# ignition2.net
KiCad netlist of a schematic drawn in EAGLE
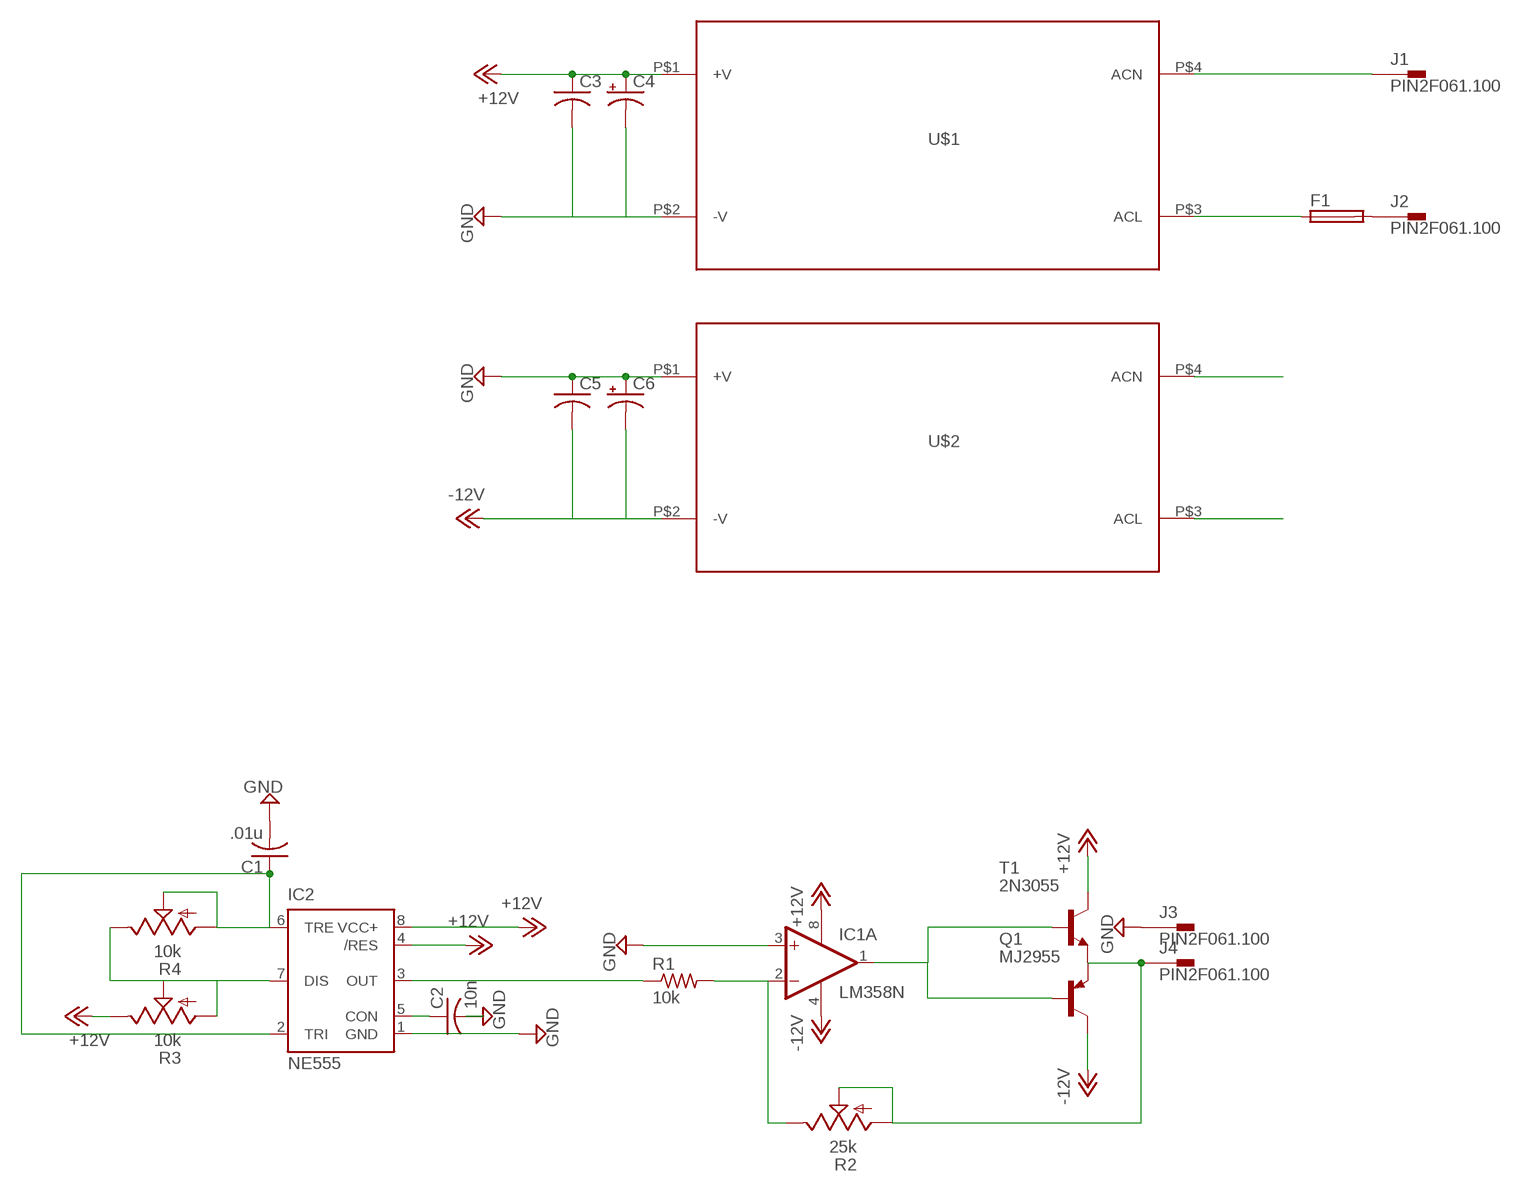
[diagram p0: schematic, sheet 1]

(export (version "E")
  (design (tool "Eeschema 10.0.6"))
  (components
    (comp (ref "C1")
      (value ".01u")
      (footprint "eagle-import:C050-035X075")
      (libsource (lib "eagle-import") (part "C-US050-035X075"))
    )
    (comp (ref "C2")
      (value "10n")
      (footprint "eagle-import:C075-042X103")
      (libsource (lib "eagle-import") (part "C-US075-042X103"))
    )
    (comp (ref "C3")
      (value "C-US050-035X075")
      (footprint "eagle-import:C050-035X075")
      (libsource (lib "eagle-import") (part "C-US050-035X075"))
    )
    (comp (ref "C4")
      (value "CPOL-USE5-5")
      (footprint "eagle-import:E5-5")
      (libsource (lib "eagle-import") (part "CPOL-USE5-5"))
    )
    (comp (ref "C5")
      (value "C-US050-035X075")
      (footprint "eagle-import:C050-035X075")
      (libsource (lib "eagle-import") (part "C-US050-035X075"))
    )
    (comp (ref "C6")
      (value "CPOL-USE5-5")
      (footprint "eagle-import:E5-5")
      (libsource (lib "eagle-import") (part "CPOL-USE5-5"))
    )
    (comp (ref "F1")
      (value "SH25")
      (footprint "eagle-import:SH25")
      (fields (field (name "MF") "SCHURTER") (field (name "MPN") "0031.8211"))
      (libsource (lib "eagle-import") (part "SH25"))
    )
    (comp (ref "IC1")
      (value "LM358N")
      (footprint "eagle-import:DIL08")
      (libsource (lib "eagle-import") (part "LM358N"))
    )
    (comp (ref "IC2")
      (value "NE555")
      (footprint "eagle-import:DIL-08")
      (fields (field (name "MF") "Arrow Electronics") (field (name "MPN") "NE555N"))
      (libsource (lib "eagle-import") (part "NE555"))
    )
    (comp (ref "J1")
      (value "PIN2F061.100")
      (footprint "eagle-import:F061.100")
      (libsource (lib "eagle-import") (part "PIN2F061.100"))
    )
    (comp (ref "J2")
      (value "PIN2F061.100")
      (footprint "eagle-import:F061.100")
      (libsource (lib "eagle-import") (part "PIN2F061.100"))
    )
    (comp (ref "J3")
      (value "PIN2F061.100")
      (footprint "eagle-import:F061.100")
      (libsource (lib "eagle-import") (part "PIN2F061.100"))
    )
    (comp (ref "J4")
      (value "PIN2F061.100")
      (footprint "eagle-import:F061.100")
      (libsource (lib "eagle-import") (part "PIN2F061.100"))
    )
    (comp (ref "Q1")
      (value "MJ2955")
      (footprint "eagle-import:TO3")
      (libsource (lib "eagle-import") (part "MJ2955"))
    )
    (comp (ref "R1")
      (value "10k")
      (footprint "eagle-import:0207_10")
      (libsource (lib "eagle-import") (part "R-US_0207/10"))
    )
    (comp (ref "R2")
      (value "25k")
      (footprint "eagle-import:B64Y")
      (libsource (lib "eagle-import") (part "TRIM_US-B64Y"))
    )
    (comp (ref "R3")
      (value "10k")
      (footprint "eagle-import:B64Y")
      (libsource (lib "eagle-import") (part "TRIM_US-B64Y"))
    )
    (comp (ref "R4")
      (value "10k")
      (footprint "eagle-import:B64Y")
      (libsource (lib "eagle-import") (part "TRIM_US-B64Y"))
    )
    (comp (ref "T1")
      (value "2N3055")
      (footprint "eagle-import:TO3")
      (libsource (lib "eagle-import") (part "2N3055"))
    )
    (comp (ref "U$1")
      (value "IRM-60-12")
      (footprint "eagle-import:IRM-60-12")
      (libsource (lib "eagle-import") (part "IRM-60-12"))
    )
    (comp (ref "U$2")
      (value "IRM-60-12")
      (footprint "eagle-import:IRM-60-12")
      (libsource (lib "eagle-import") (part "IRM-60-12"))
    )
  )
  (nets
    (net (code "1") (name "+12V") (class "Default")
      (node (ref "C3") (pin "1") (pinfunction "1_1") (pintype "passive"))
      (node (ref "C4") (pin "+") (pinfunction "+_+") (pintype "passive"))
      (node (ref "IC1") (pin "8") (pinfunction "V+_8") (pintype "power_in"))
      (node (ref "IC2") (pin "4") (pinfunction "/RES_4") (pintype "input"))
      (node (ref "IC2") (pin "8") (pinfunction "VCC+_8") (pintype "power_in"))
      (node (ref "R3") (pin "E") (pinfunction "E_E") (pintype "passive"))
      (node (ref "T1") (pin "C") (pinfunction "C_C") (pintype "passive"))
      (node (ref "T1") (pin "C/") (pinfunction "C_C/") (pintype "passive"))
      (node (ref "U$1") (pin "P$1") (pinfunction "+V_P$1") (pintype "bidirectional"))
    )
    (net (code "2") (name "-12V") (class "Default")
      (node (ref "C5") (pin "2") (pinfunction "2_2") (pintype "passive"))
      (node (ref "C6") (pin "-") (pinfunction "-_-") (pintype "passive"))
      (node (ref "IC1") (pin "4") (pinfunction "V-_4") (pintype "power_in"))
      (node (ref "Q1") (pin "C") (pinfunction "C_C") (pintype "passive"))
      (node (ref "Q1") (pin "C/") (pinfunction "C_C/") (pintype "passive"))
      (node (ref "U$2") (pin "P$2") (pinfunction "-V_P$2") (pintype "bidirectional"))
    )
    (net (code "3") (name "/L") (class "Default")
      (node (ref "F1") (pin "1") (pinfunction "1_1") (pintype "passive"))
      (node (ref "U$1") (pin "P$3") (pinfunction "ACL_P$3") (pintype "bidirectional"))
      (node (ref "U$2") (pin "P$3") (pinfunction "ACL_P$3") (pintype "bidirectional"))
    )
    (net (code "4") (name "/N") (class "Default")
      (node (ref "J1") (pin "A1") (pinfunction "1_A1") (pintype "passive"))
      (node (ref "J1") (pin "A2") (pinfunction "1_A2") (pintype "passive"))
      (node (ref "U$1") (pin "P$4") (pinfunction "ACN_P$4") (pintype "bidirectional"))
      (node (ref "U$2") (pin "P$4") (pinfunction "ACN_P$4") (pintype "bidirectional"))
    )
    (net (code "5") (name "GND") (class "Default")
      (node (ref "C1") (pin "2") (pinfunction "2_2") (pintype "passive"))
      (node (ref "C2") (pin "2") (pinfunction "2_2") (pintype "passive"))
      (node (ref "C3") (pin "2") (pinfunction "2_2") (pintype "passive"))
      (node (ref "C4") (pin "-") (pinfunction "-_-") (pintype "passive"))
      (node (ref "C5") (pin "1") (pinfunction "1_1") (pintype "passive"))
      (node (ref "C6") (pin "+") (pinfunction "+_+") (pintype "passive"))
      (node (ref "IC1") (pin "3") (pinfunction "+IN_3") (pintype "input"))
      (node (ref "IC2") (pin "1") (pinfunction "GND_1") (pintype "power_in"))
      (node (ref "J3") (pin "A1") (pinfunction "1_A1") (pintype "passive"))
      (node (ref "J3") (pin "A2") (pinfunction "1_A2") (pintype "passive"))
      (node (ref "U$1") (pin "P$2") (pinfunction "-V_P$2") (pintype "bidirectional"))
      (node (ref "U$2") (pin "P$1") (pinfunction "+V_P$1") (pintype "bidirectional"))
    )
    (net (code "6") (name "Net-(F1-Pad2)") (class "Default")
      (node (ref "F1") (pin "2") (pinfunction "2_2") (pintype "passive"))
      (node (ref "J2") (pin "A1") (pinfunction "1_A1") (pintype "passive"))
      (node (ref "J2") (pin "A2") (pinfunction "1_A2") (pintype "passive"))
    )
    (net (code "7") (name "Net-(IC1A--IN)") (class "Default")
      (node (ref "IC1") (pin "2") (pinfunction "-IN_2") (pintype "input"))
      (node (ref "R1") (pin "2") (pinfunction "2_2") (pintype "passive"))
      (node (ref "R2") (pin "E") (pinfunction "E_E") (pintype "passive"))
    )
    (net (code "8") (name "Net-(IC1A-OUT)") (class "Default")
      (node (ref "IC1") (pin "1") (pinfunction "OUT_1") (pintype "output"))
      (node (ref "Q1") (pin "B") (pinfunction "B_B") (pintype "passive"))
      (node (ref "T1") (pin "B") (pinfunction "B_B") (pintype "passive"))
    )
    (net (code "9") (name "Net-(IC2-CON)") (class "Default")
      (node (ref "C2") (pin "1") (pinfunction "1_1") (pintype "passive"))
      (node (ref "IC2") (pin "5") (pinfunction "CON_5") (pintype "input"))
    )
    (net (code "10") (name "Net-(IC2-DIS)") (class "Default")
      (node (ref "IC2") (pin "7") (pinfunction "DIS_7") (pintype "input"))
      (node (ref "R3") (pin "A") (pinfunction "A_A") (pintype "passive"))
      (node (ref "R3") (pin "S") (pinfunction "S_S") (pintype "passive"))
      (node (ref "R4") (pin "E") (pinfunction "E_E") (pintype "passive"))
    )
    (net (code "11") (name "Net-(IC2-OUT)") (class "Default")
      (node (ref "IC2") (pin "3") (pinfunction "OUT_3") (pintype "output"))
      (node (ref "R1") (pin "1") (pinfunction "1_1") (pintype "passive"))
    )
    (net (code "12") (name "Net-(IC2-TRE)") (class "Default")
      (node (ref "C1") (pin "1") (pinfunction "1_1") (pintype "passive"))
      (node (ref "IC2") (pin "2") (pinfunction "TRI_2") (pintype "input"))
      (node (ref "IC2") (pin "6") (pinfunction "TRE_6") (pintype "input"))
      (node (ref "R4") (pin "A") (pinfunction "A_A") (pintype "passive"))
      (node (ref "R4") (pin "S") (pinfunction "S_S") (pintype "passive"))
    )
    (net (code "13") (name "Net-(J4-1-PadA1)") (class "Default")
      (node (ref "J4") (pin "A1") (pinfunction "1_A1") (pintype "passive"))
      (node (ref "J4") (pin "A2") (pinfunction "1_A2") (pintype "passive"))
      (node (ref "Q1") (pin "E") (pinfunction "E_E") (pintype "passive"))
      (node (ref "R2") (pin "A") (pinfunction "A_A") (pintype "passive"))
      (node (ref "R2") (pin "S") (pinfunction "S_S") (pintype "passive"))
      (node (ref "T1") (pin "E") (pinfunction "E_E") (pintype "passive"))
    )
  )
)
